# main.net
KiCad netlist of a schematic drawn in EAGLE
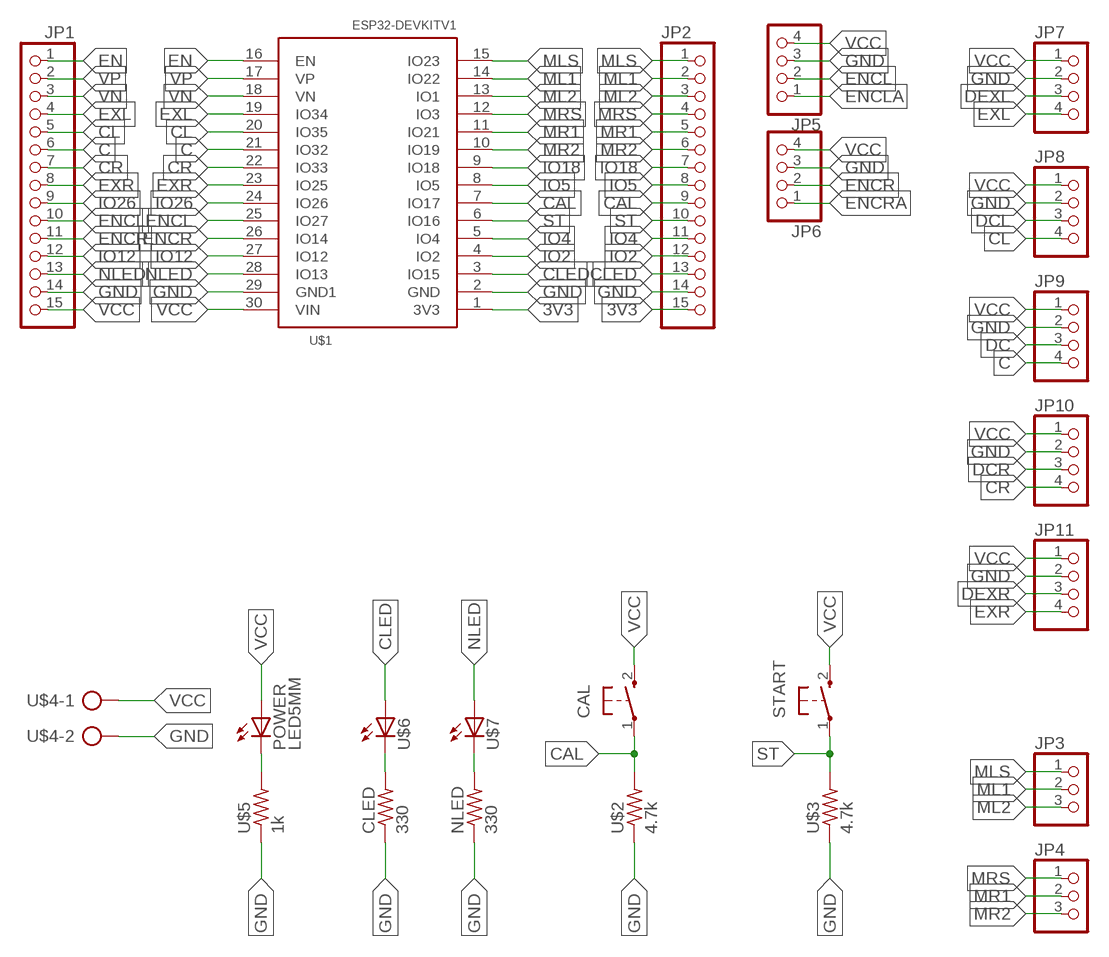
[diagram p0: schematic, sheet 1]

(export (version "E")
  (design (tool "Eeschema 10.0.6"))
  (components
    (comp (ref "CAL")
      (value "PUSH_BUTTON")
      (footprint "eagle-import:B3F-10XX")
      (libsource (lib "eagle-import") (part "PUSH_BUTTON"))
    )
    (comp (ref "CLED")
      (value "330")
      (footprint "eagle-import:0204_7")
      (libsource (lib "eagle-import") (part "RES-7"))
    )
    (comp (ref "JP1")
      (value "PINHD-1X15")
      (footprint "eagle-import:1X15")
      (libsource (lib "eagle-import") (part "PINHD-1X15"))
    )
    (comp (ref "JP2")
      (value "PINHD-1X15")
      (footprint "eagle-import:1X15")
      (libsource (lib "eagle-import") (part "PINHD-1X15"))
    )
    (comp (ref "JP3")
      (value "PINHD-1X3")
      (footprint "eagle-import:1X03")
      (libsource (lib "eagle-import") (part "PINHD-1X3"))
    )
    (comp (ref "JP4")
      (value "PINHD-1X3")
      (footprint "eagle-import:1X03")
      (libsource (lib "eagle-import") (part "PINHD-1X3"))
    )
    (comp (ref "JP5")
      (value "PINHD-1X4")
      (footprint "eagle-import:1X04")
      (libsource (lib "eagle-import") (part "PINHD-1X4"))
    )
    (comp (ref "JP6")
      (value "PINHD-1X4")
      (footprint "eagle-import:1X04")
      (libsource (lib "eagle-import") (part "PINHD-1X4"))
    )
    (comp (ref "JP7")
      (value "PINHD-1X4")
      (footprint "eagle-import:1X04")
      (libsource (lib "eagle-import") (part "PINHD-1X4"))
    )
    (comp (ref "JP8")
      (value "PINHD-1X4")
      (footprint "eagle-import:1X04")
      (libsource (lib "eagle-import") (part "PINHD-1X4"))
    )
    (comp (ref "JP9")
      (value "PINHD-1X4")
      (footprint "eagle-import:1X04")
      (libsource (lib "eagle-import") (part "PINHD-1X4"))
    )
    (comp (ref "JP10")
      (value "PINHD-1X4")
      (footprint "eagle-import:1X04")
      (libsource (lib "eagle-import") (part "PINHD-1X4"))
    )
    (comp (ref "JP11")
      (value "PINHD-1X4")
      (footprint "eagle-import:1X04")
      (libsource (lib "eagle-import") (part "PINHD-1X4"))
    )
    (comp (ref "NLED")
      (value "330")
      (footprint "eagle-import:0204_7")
      (libsource (lib "eagle-import") (part "RES-7"))
    )
    (comp (ref "POWER")
      (value "LED5MM")
      (footprint "eagle-import:LED5MM")
      (libsource (lib "eagle-import") (part "LED5MM"))
    )
    (comp (ref "START")
      (value "PUSH_BUTTON")
      (footprint "eagle-import:B3F-10XX")
      (libsource (lib "eagle-import") (part "PUSH_BUTTON"))
    )
    (comp (ref "U$1")
      (value "ESP32DEVKITV1")
      (footprint "eagle-import:ESP32-DEVKITV1")
      (libsource (lib "eagle-import") (part "ESP32DEVKITV1"))
    )
    (comp (ref "U$2")
      (value "4.7k")
      (footprint "eagle-import:0204_7")
      (libsource (lib "eagle-import") (part "RES-7"))
    )
    (comp (ref "U$3")
      (value "4.7k")
      (footprint "eagle-import:0204_7")
      (libsource (lib "eagle-import") (part "RES-7"))
    )
    (comp (ref "U$4")
      (value "CON_PTR_2(V_2)")
      (footprint "eagle-import:AK300_2")
      (libsource (lib "eagle-import") (part "CON_PTR_2(V_2)"))
    )
    (comp (ref "U$5")
      (value "1k")
      (footprint "eagle-import:0204_7")
      (libsource (lib "eagle-import") (part "RES-7"))
    )
    (comp (ref "U$6")
      (value "LED5MM")
      (footprint "eagle-import:LED5MM")
      (libsource (lib "eagle-import") (part "LED5MM"))
    )
    (comp (ref "U$7")
      (value "LED5MM")
      (footprint "eagle-import:LED5MM")
      (libsource (lib "eagle-import") (part "LED5MM"))
    )
  )
  (nets
    (net (code "1") (name "3V3") (class "Default")
      (node (ref "JP2") (pin "15") (pinfunction "15_15") (pintype "passive"))
      (node (ref "U$1") (pin "1") (pinfunction "3V3_1") (pintype "bidirectional"))
    )
    (net (code "2") (name "C") (class "Default")
      (node (ref "JP1") (pin "6") (pinfunction "6_6") (pintype "passive"))
      (node (ref "JP9") (pin "4") (pinfunction "4_4") (pintype "passive"))
      (node (ref "U$1") (pin "21") (pinfunction "IO32_21") (pintype "bidirectional"))
    )
    (net (code "3") (name "CAL") (class "Default")
      (node (ref "CAL") (pin "1") (pinfunction "P_1") (pintype "passive"))
      (node (ref "JP2") (pin "9") (pinfunction "9_9") (pintype "passive"))
      (node (ref "U$1") (pin "7") (pinfunction "IO17_7") (pintype "bidirectional"))
      (node (ref "U$2") (pin "2") (pinfunction "2_2") (pintype "passive"))
    )
    (net (code "4") (name "CL") (class "Default")
      (node (ref "JP1") (pin "5") (pinfunction "5_5") (pintype "passive"))
      (node (ref "JP8") (pin "4") (pinfunction "4_4") (pintype "passive"))
      (node (ref "U$1") (pin "20") (pinfunction "IO35_20") (pintype "bidirectional"))
    )
    (net (code "5") (name "CLED") (class "Default")
      (node (ref "JP2") (pin "13") (pinfunction "13_13") (pintype "passive"))
      (node (ref "U$1") (pin "3") (pinfunction "IO15_3") (pintype "bidirectional"))
      (node (ref "U$6") (pin "A") (pinfunction "A_A") (pintype "passive"))
    )
    (net (code "6") (name "CR") (class "Default")
      (node (ref "JP1") (pin "7") (pinfunction "7_7") (pintype "passive"))
      (node (ref "JP10") (pin "4") (pinfunction "4_4") (pintype "passive"))
      (node (ref "U$1") (pin "22") (pinfunction "IO33_22") (pintype "bidirectional"))
    )
    (net (code "7") (name "DC") (class "Default")
      (node (ref "JP9") (pin "3") (pinfunction "3_3") (pintype "passive"))
    )
    (net (code "8") (name "DCL") (class "Default")
      (node (ref "JP8") (pin "3") (pinfunction "3_3") (pintype "passive"))
    )
    (net (code "9") (name "DCR") (class "Default")
      (node (ref "JP10") (pin "3") (pinfunction "3_3") (pintype "passive"))
    )
    (net (code "10") (name "DEXL") (class "Default")
      (node (ref "JP7") (pin "3") (pinfunction "3_3") (pintype "passive"))
    )
    (net (code "11") (name "DEXR") (class "Default")
      (node (ref "JP11") (pin "3") (pinfunction "3_3") (pintype "passive"))
    )
    (net (code "12") (name "EN") (class "Default")
      (node (ref "JP1") (pin "1") (pinfunction "1_1") (pintype "passive"))
      (node (ref "U$1") (pin "16") (pinfunction "EN_16") (pintype "bidirectional"))
    )
    (net (code "13") (name "ENCL") (class "Default")
      (node (ref "JP1") (pin "10") (pinfunction "10_10") (pintype "passive"))
      (node (ref "JP5") (pin "2") (pinfunction "2_2") (pintype "passive"))
      (node (ref "U$1") (pin "25") (pinfunction "IO27_25") (pintype "bidirectional"))
    )
    (net (code "14") (name "ENCLA") (class "Default")
      (node (ref "JP5") (pin "1") (pinfunction "1_1") (pintype "passive"))
    )
    (net (code "15") (name "ENCR") (class "Default")
      (node (ref "JP1") (pin "11") (pinfunction "11_11") (pintype "passive"))
      (node (ref "JP6") (pin "2") (pinfunction "2_2") (pintype "passive"))
      (node (ref "U$1") (pin "26") (pinfunction "IO14_26") (pintype "bidirectional"))
    )
    (net (code "16") (name "ENCRA") (class "Default")
      (node (ref "JP6") (pin "1") (pinfunction "1_1") (pintype "passive"))
    )
    (net (code "17") (name "EXL") (class "Default")
      (node (ref "JP1") (pin "4") (pinfunction "4_4") (pintype "passive"))
      (node (ref "JP7") (pin "4") (pinfunction "4_4") (pintype "passive"))
      (node (ref "U$1") (pin "19") (pinfunction "IO34_19") (pintype "bidirectional"))
    )
    (net (code "18") (name "EXR") (class "Default")
      (node (ref "JP1") (pin "8") (pinfunction "8_8") (pintype "passive"))
      (node (ref "JP11") (pin "4") (pinfunction "4_4") (pintype "passive"))
      (node (ref "U$1") (pin "23") (pinfunction "IO25_23") (pintype "bidirectional"))
    )
    (net (code "19") (name "GND") (class "Default")
      (node (ref "CLED") (pin "1") (pinfunction "1_1") (pintype "passive"))
      (node (ref "JP1") (pin "14") (pinfunction "14_14") (pintype "passive"))
      (node (ref "JP10") (pin "2") (pinfunction "2_2") (pintype "passive"))
      (node (ref "JP11") (pin "2") (pinfunction "2_2") (pintype "passive"))
      (node (ref "JP2") (pin "14") (pinfunction "14_14") (pintype "passive"))
      (node (ref "JP5") (pin "3") (pinfunction "3_3") (pintype "passive"))
      (node (ref "JP6") (pin "3") (pinfunction "3_3") (pintype "passive"))
      (node (ref "JP7") (pin "2") (pinfunction "2_2") (pintype "passive"))
      (node (ref "JP8") (pin "2") (pinfunction "2_2") (pintype "passive"))
      (node (ref "JP9") (pin "2") (pinfunction "2_2") (pintype "passive"))
      (node (ref "NLED") (pin "1") (pinfunction "1_1") (pintype "passive"))
      (node (ref "U$1") (pin "2") (pinfunction "GND_2") (pintype "bidirectional"))
      (node (ref "U$1") (pin "29") (pinfunction "GND1_29") (pintype "bidirectional"))
      (node (ref "U$2") (pin "1") (pinfunction "1_1") (pintype "passive"))
      (node (ref "U$3") (pin "1") (pinfunction "1_1") (pintype "passive"))
      (node (ref "U$4") (pin "2") (pinfunction "KL_2") (pintype "passive"))
      (node (ref "U$5") (pin "1") (pinfunction "1_1") (pintype "passive"))
    )
    (net (code "20") (name "IO2") (class "Default")
      (node (ref "JP2") (pin "12") (pinfunction "12_12") (pintype "passive"))
      (node (ref "U$1") (pin "4") (pinfunction "IO2_4") (pintype "bidirectional"))
    )
    (net (code "21") (name "IO4") (class "Default")
      (node (ref "JP2") (pin "11") (pinfunction "11_11") (pintype "passive"))
      (node (ref "U$1") (pin "5") (pinfunction "IO4_5") (pintype "bidirectional"))
    )
    (net (code "22") (name "IO5") (class "Default")
      (node (ref "JP2") (pin "8") (pinfunction "8_8") (pintype "passive"))
      (node (ref "U$1") (pin "8") (pinfunction "IO5_8") (pintype "bidirectional"))
    )
    (net (code "23") (name "IO12") (class "Default")
      (node (ref "JP1") (pin "12") (pinfunction "12_12") (pintype "passive"))
      (node (ref "U$1") (pin "27") (pinfunction "IO12_27") (pintype "bidirectional"))
    )
    (net (code "24") (name "IO18") (class "Default")
      (node (ref "JP2") (pin "7") (pinfunction "7_7") (pintype "passive"))
      (node (ref "U$1") (pin "9") (pinfunction "IO18_9") (pintype "bidirectional"))
    )
    (net (code "25") (name "IO26") (class "Default")
      (node (ref "JP1") (pin "9") (pinfunction "9_9") (pintype "passive"))
      (node (ref "U$1") (pin "24") (pinfunction "IO26_24") (pintype "bidirectional"))
    )
    (net (code "26") (name "ML1") (class "Default")
      (node (ref "JP2") (pin "2") (pinfunction "2_2") (pintype "passive"))
      (node (ref "JP3") (pin "2") (pinfunction "2_2") (pintype "passive"))
      (node (ref "U$1") (pin "14") (pinfunction "IO22_14") (pintype "bidirectional"))
    )
    (net (code "27") (name "ML2") (class "Default")
      (node (ref "JP2") (pin "3") (pinfunction "3_3") (pintype "passive"))
      (node (ref "JP3") (pin "3") (pinfunction "3_3") (pintype "passive"))
      (node (ref "U$1") (pin "13") (pinfunction "IO1_13") (pintype "bidirectional"))
    )
    (net (code "28") (name "MLS") (class "Default")
      (node (ref "JP2") (pin "1") (pinfunction "1_1") (pintype "passive"))
      (node (ref "JP3") (pin "1") (pinfunction "1_1") (pintype "passive"))
      (node (ref "U$1") (pin "15") (pinfunction "IO23_15") (pintype "bidirectional"))
    )
    (net (code "29") (name "MR1") (class "Default")
      (node (ref "JP2") (pin "5") (pinfunction "5_5") (pintype "passive"))
      (node (ref "JP4") (pin "2") (pinfunction "2_2") (pintype "passive"))
      (node (ref "U$1") (pin "11") (pinfunction "IO21_11") (pintype "bidirectional"))
    )
    (net (code "30") (name "MR2") (class "Default")
      (node (ref "JP2") (pin "6") (pinfunction "6_6") (pintype "passive"))
      (node (ref "JP4") (pin "3") (pinfunction "3_3") (pintype "passive"))
      (node (ref "U$1") (pin "10") (pinfunction "IO19_10") (pintype "bidirectional"))
    )
    (net (code "31") (name "MRS") (class "Default")
      (node (ref "JP2") (pin "4") (pinfunction "4_4") (pintype "passive"))
      (node (ref "JP4") (pin "1") (pinfunction "1_1") (pintype "passive"))
      (node (ref "U$1") (pin "12") (pinfunction "IO3_12") (pintype "bidirectional"))
    )
    (net (code "32") (name "NLED") (class "Default")
      (node (ref "JP1") (pin "13") (pinfunction "13_13") (pintype "passive"))
      (node (ref "U$1") (pin "28") (pinfunction "IO13_28") (pintype "bidirectional"))
      (node (ref "U$7") (pin "A") (pinfunction "A_A") (pintype "passive"))
    )
    (net (code "33") (name "Net-(POWER-C)") (class "Default")
      (node (ref "POWER") (pin "K") (pinfunction "C_K") (pintype "passive"))
      (node (ref "U$5") (pin "2") (pinfunction "2_2") (pintype "passive"))
    )
    (net (code "34") (name "Net-(U$6-C)") (class "Default")
      (node (ref "CLED") (pin "2") (pinfunction "2_2") (pintype "passive"))
      (node (ref "U$6") (pin "K") (pinfunction "C_K") (pintype "passive"))
    )
    (net (code "35") (name "Net-(U$7-C)") (class "Default")
      (node (ref "NLED") (pin "2") (pinfunction "2_2") (pintype "passive"))
      (node (ref "U$7") (pin "K") (pinfunction "C_K") (pintype "passive"))
    )
    (net (code "36") (name "ST") (class "Default")
      (node (ref "JP2") (pin "10") (pinfunction "10_10") (pintype "passive"))
      (node (ref "START") (pin "1") (pinfunction "P_1") (pintype "passive"))
      (node (ref "U$1") (pin "6") (pinfunction "IO16_6") (pintype "bidirectional"))
      (node (ref "U$3") (pin "2") (pinfunction "2_2") (pintype "passive"))
    )
    (net (code "37") (name "VCC") (class "Default")
      (node (ref "CAL") (pin "2") (pinfunction "S_2") (pintype "passive"))
      (node (ref "JP1") (pin "15") (pinfunction "15_15") (pintype "passive"))
      (node (ref "JP10") (pin "1") (pinfunction "1_1") (pintype "passive"))
      (node (ref "JP11") (pin "1") (pinfunction "1_1") (pintype "passive"))
      (node (ref "JP5") (pin "4") (pinfunction "4_4") (pintype "passive"))
      (node (ref "JP6") (pin "4") (pinfunction "4_4") (pintype "passive"))
      (node (ref "JP7") (pin "1") (pinfunction "1_1") (pintype "passive"))
      (node (ref "JP8") (pin "1") (pinfunction "1_1") (pintype "passive"))
      (node (ref "JP9") (pin "1") (pinfunction "1_1") (pintype "passive"))
      (node (ref "POWER") (pin "A") (pinfunction "A_A") (pintype "passive"))
      (node (ref "START") (pin "2") (pinfunction "S_2") (pintype "passive"))
      (node (ref "U$1") (pin "30") (pinfunction "VIN_30") (pintype "bidirectional"))
      (node (ref "U$4") (pin "1") (pinfunction "KL_1") (pintype "passive"))
    )
    (net (code "38") (name "VN") (class "Default")
      (node (ref "JP1") (pin "3") (pinfunction "3_3") (pintype "passive"))
      (node (ref "U$1") (pin "18") (pinfunction "VN_18") (pintype "bidirectional"))
    )
    (net (code "39") (name "VP") (class "Default")
      (node (ref "JP1") (pin "2") (pinfunction "2_2") (pintype "passive"))
      (node (ref "U$1") (pin "17") (pinfunction "VP_17") (pintype "bidirectional"))
    )
  )
)
